# Lora_LR1262_Node__Board_V1_0_1.net
KiCad netlist of a schematic drawn in EAGLE
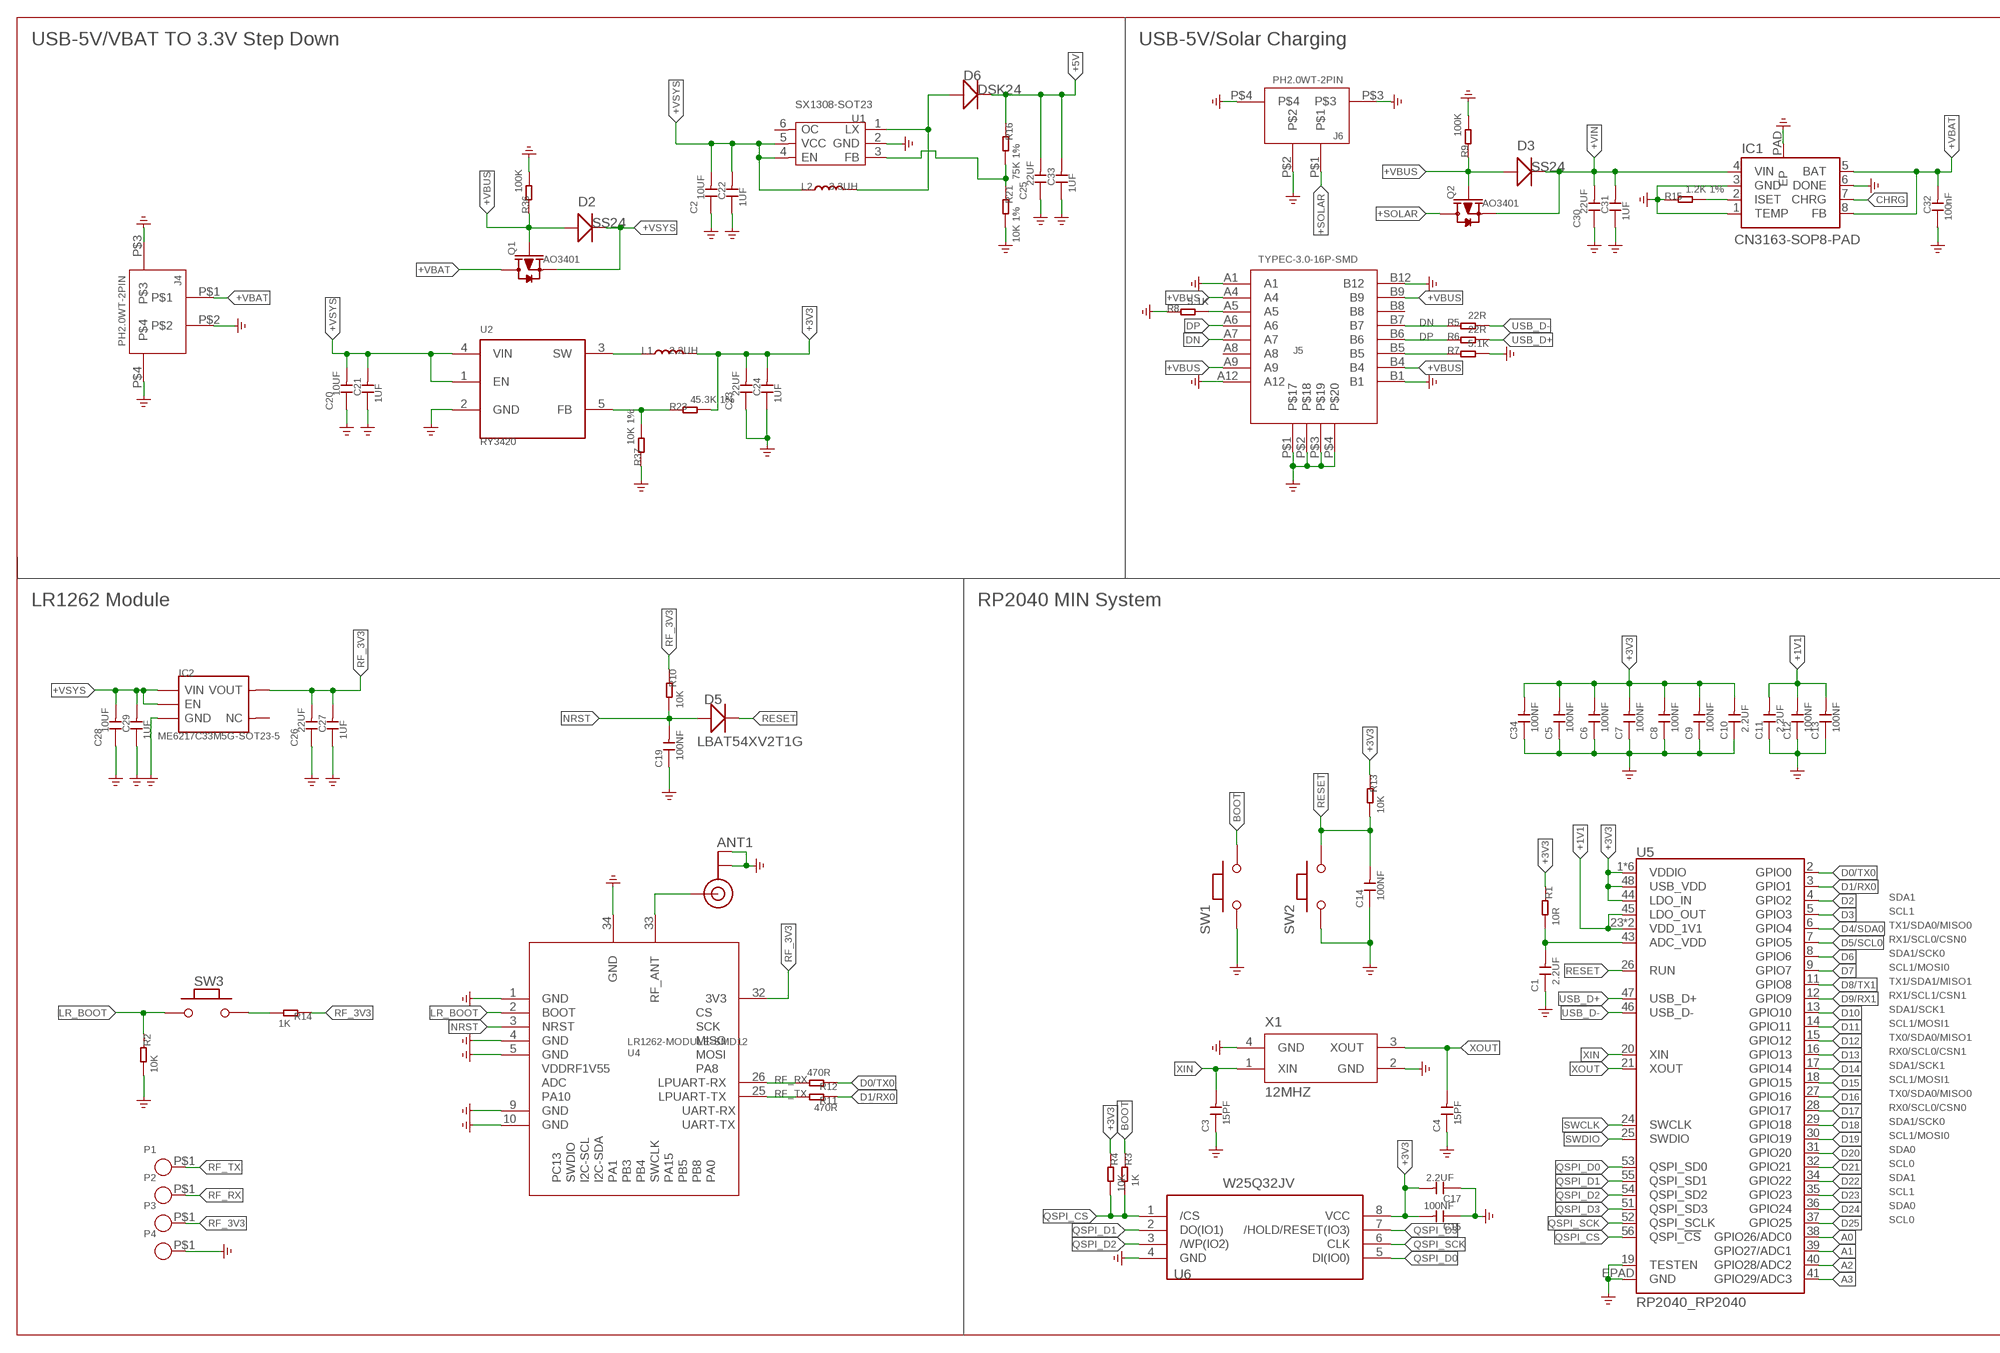
[diagram p0: schematic, sheet 1, part 1 of 2]
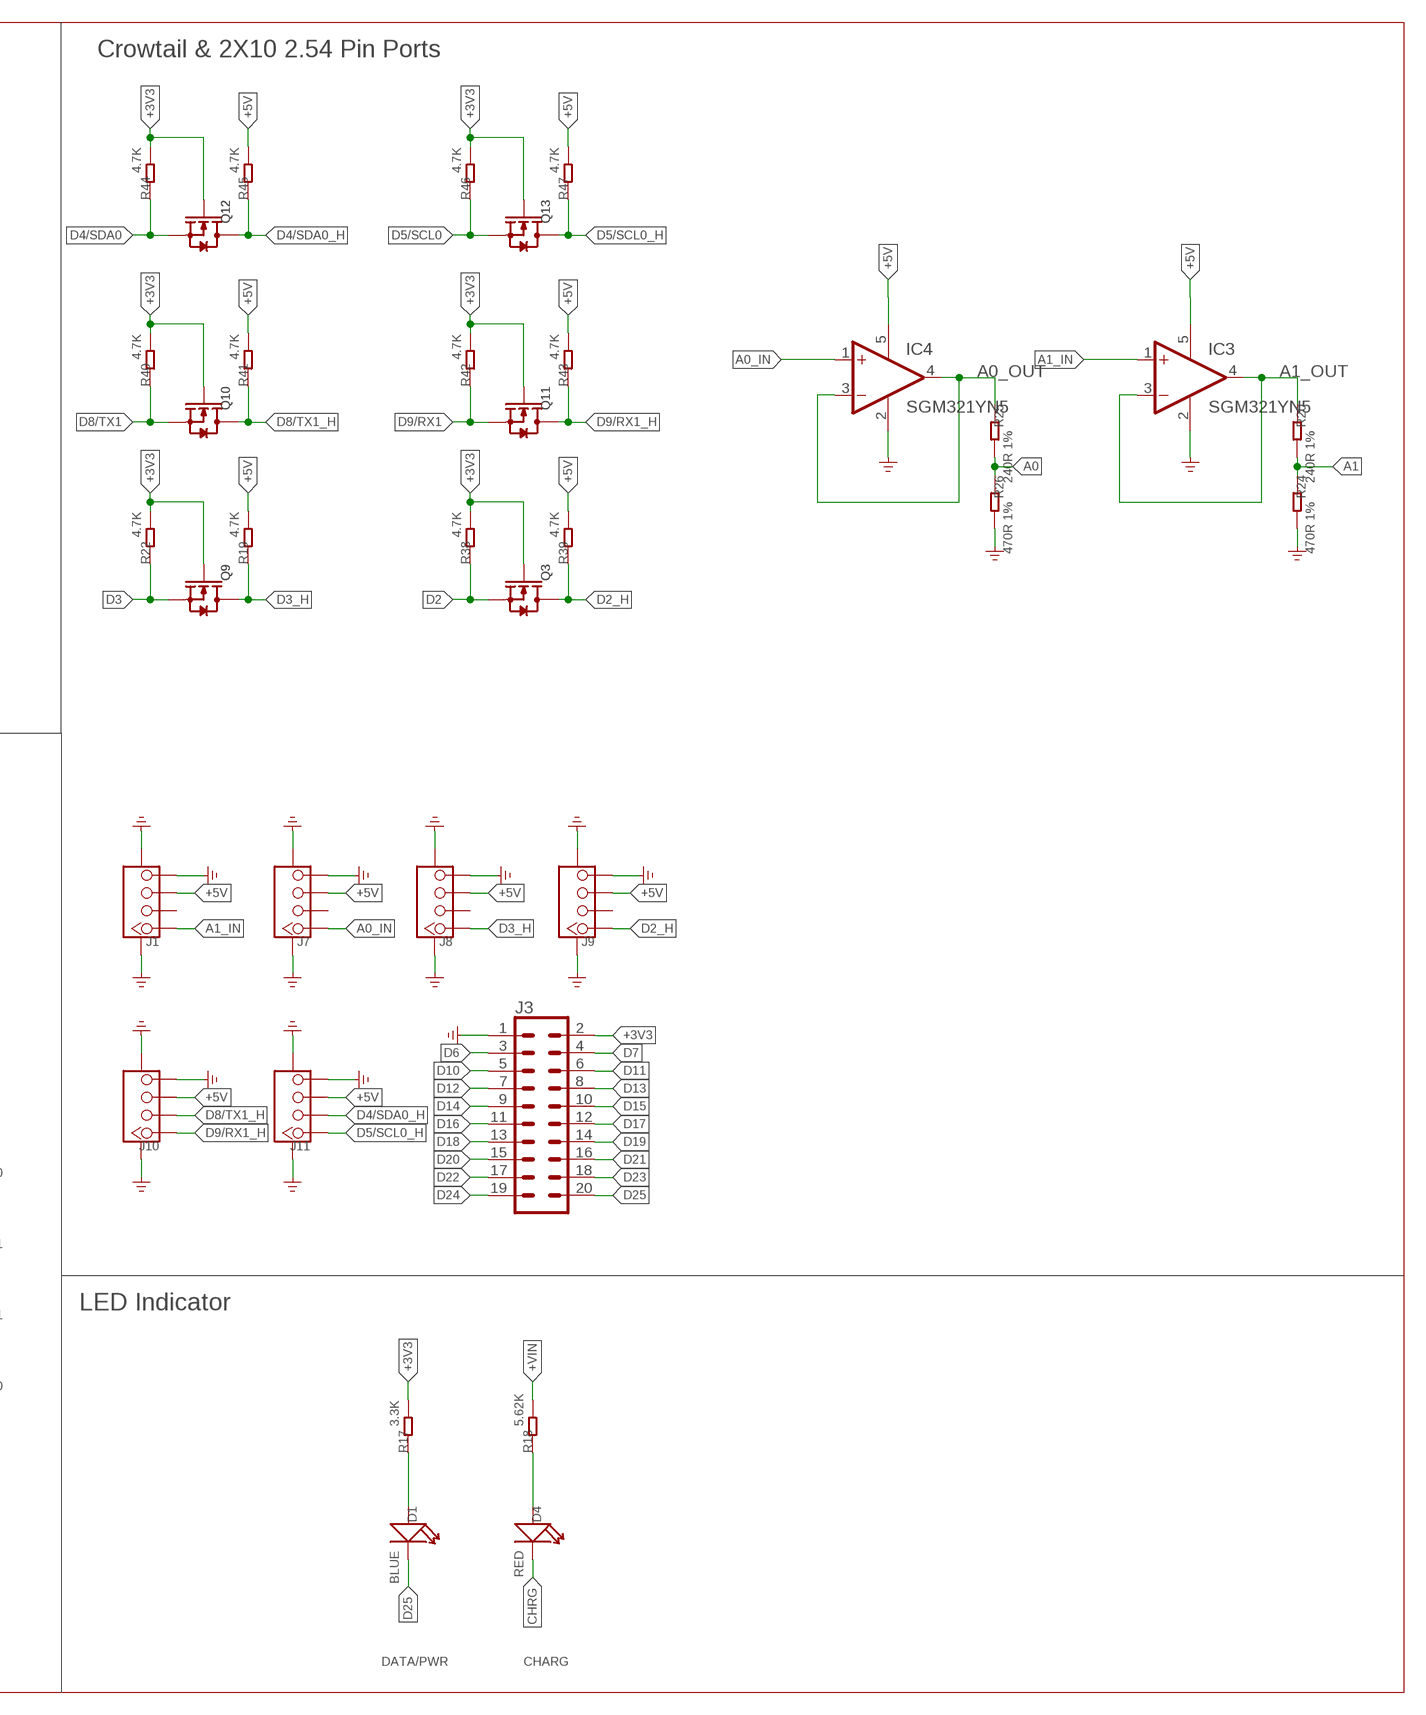
[diagram p1: schematic, sheet 1, part 2 of 2]

(export (version "E")
  (design (tool "Eeschema 10.0.6"))
  (components
    (comp (ref "ANT1")
      (value "SPARKFUN2_U.FL")
      (footprint "eagle-import:SPARKFUN2_U.FL")
      (libsource (lib "eagle-import") (part "SPARKFUN2_U.FL"))
    )
    (comp (ref "C1")
      (value "2.2UF")
      (footprint "eagle-import:0402")
      (libsource (lib "eagle-import") (part "CAPC0402-1"))
    )
    (comp (ref "C2")
      (value "10UF")
      (footprint "eagle-import:C0805")
      (libsource (lib "eagle-import") (part "C0805"))
    )
    (comp (ref "C3")
      (value "15PF")
      (footprint "eagle-import:0402")
      (libsource (lib "eagle-import") (part "CAPC0402-1"))
    )
    (comp (ref "C4")
      (value "15PF")
      (footprint "eagle-import:0402")
      (libsource (lib "eagle-import") (part "CAPC0402-1"))
    )
    (comp (ref "C5")
      (value "100NF")
      (footprint "eagle-import:0402")
      (libsource (lib "eagle-import") (part "CAPC0402-1"))
    )
    (comp (ref "C6")
      (value "100NF")
      (footprint "eagle-import:0402")
      (libsource (lib "eagle-import") (part "CAPC0402-1"))
    )
    (comp (ref "C7")
      (value "100NF")
      (footprint "eagle-import:0402")
      (libsource (lib "eagle-import") (part "CAPC0402-1"))
    )
    (comp (ref "C8")
      (value "100NF")
      (footprint "eagle-import:0402")
      (libsource (lib "eagle-import") (part "CAPC0402-1"))
    )
    (comp (ref "C9")
      (value "100NF")
      (footprint "eagle-import:0402")
      (libsource (lib "eagle-import") (part "CAPC0402-1"))
    )
    (comp (ref "C10")
      (value "2.2UF")
      (footprint "eagle-import:0402")
      (libsource (lib "eagle-import") (part "CAPC0402-1"))
    )
    (comp (ref "C11")
      (value "2.2UF")
      (footprint "eagle-import:0402")
      (libsource (lib "eagle-import") (part "CAPC0402-1"))
    )
    (comp (ref "C12")
      (value "100NF")
      (footprint "eagle-import:0402")
      (libsource (lib "eagle-import") (part "CAPC0402-1"))
    )
    (comp (ref "C13")
      (value "100NF")
      (footprint "eagle-import:0402")
      (libsource (lib "eagle-import") (part "CAPC0402-1"))
    )
    (comp (ref "C14")
      (value "100NF")
      (footprint "eagle-import:0402")
      (libsource (lib "eagle-import") (part "CAPC0402-1"))
    )
    (comp (ref "C15")
      (value "100NF")
      (footprint "eagle-import:0402")
      (libsource (lib "eagle-import") (part "CAPC0402-1"))
    )
    (comp (ref "C17")
      (value "2.2UF")
      (footprint "eagle-import:0402")
      (libsource (lib "eagle-import") (part "CAPC0402-1"))
    )
    (comp (ref "C19")
      (value "100NF")
      (footprint "eagle-import:0402")
      (libsource (lib "eagle-import") (part "CAPC0402-1"))
    )
    (comp (ref "C20")
      (value "10UF")
      (footprint "eagle-import:C0805")
      (libsource (lib "eagle-import") (part "C0805"))
    )
    (comp (ref "C21")
      (value "1UF")
      (footprint "eagle-import:C0603")
      (libsource (lib "eagle-import") (part "C0603"))
    )
    (comp (ref "C22")
      (value "1UF")
      (footprint "eagle-import:C0603")
      (libsource (lib "eagle-import") (part "C0603"))
    )
    (comp (ref "C23")
      (value "22UF")
      (footprint "eagle-import:C0805")
      (libsource (lib "eagle-import") (part "C0805"))
    )
    (comp (ref "C24")
      (value "1UF")
      (footprint "eagle-import:C0603")
      (libsource (lib "eagle-import") (part "C0603"))
    )
    (comp (ref "C25")
      (value "22UF")
      (footprint "eagle-import:C0805")
      (libsource (lib "eagle-import") (part "C0805"))
    )
    (comp (ref "C26")
      (value "22UF")
      (footprint "eagle-import:C0805")
      (libsource (lib "eagle-import") (part "C0805"))
    )
    (comp (ref "C27")
      (value "1UF")
      (footprint "eagle-import:C0603")
      (libsource (lib "eagle-import") (part "C0603"))
    )
    (comp (ref "C28")
      (value "10UF")
      (footprint "eagle-import:C0805")
      (libsource (lib "eagle-import") (part "C0805"))
    )
    (comp (ref "C29")
      (value "1UF")
      (footprint "eagle-import:C0603")
      (libsource (lib "eagle-import") (part "C0603"))
    )
    (comp (ref "C30")
      (value "22UF")
      (footprint "eagle-import:C0805")
      (libsource (lib "eagle-import") (part "C0805"))
    )
    (comp (ref "C31")
      (value "1UF")
      (footprint "eagle-import:C0603")
      (libsource (lib "eagle-import") (part "C0603"))
    )
    (comp (ref "C32")
      (value "100nF")
      (footprint "eagle-import:C0603")
      (libsource (lib "eagle-import") (part "C0603"))
    )
    (comp (ref "C33")
      (value "1UF")
      (footprint "eagle-import:C0603")
      (libsource (lib "eagle-import") (part "C0603"))
    )
    (comp (ref "C34")
      (value "100NF")
      (footprint "eagle-import:0402")
      (libsource (lib "eagle-import") (part "CAPC0402-1"))
    )
    (comp (ref "D1")
      (value "BLUE")
      (footprint "eagle-import:LED0603")
      (libsource (lib "eagle-import") (part "LED-SMT0603"))
    )
    (comp (ref "D2")
      (value "SS24")
      (footprint "eagle-import:SMA")
      (libsource (lib "eagle-import") (part "DIODEB130L-13-F"))
    )
    (comp (ref "D3")
      (value "SS24")
      (footprint "eagle-import:SMA")
      (libsource (lib "eagle-import") (part "DIODEB130L-13-F"))
    )
    (comp (ref "D4")
      (value "RED")
      (footprint "eagle-import:LED0603")
      (libsource (lib "eagle-import") (part "LED-SMT0603"))
    )
    (comp (ref "D5")
      (value "LBAT54XV2T1G")
      (footprint "eagle-import:D_SOD523")
      (libsource (lib "eagle-import") (part "DIODE0603"))
    )
    (comp (ref "D6")
      (value "DSK24")
      (footprint "eagle-import:D_SOD123FL")
      (libsource (lib "eagle-import") (part "DIODE"))
    )
    (comp (ref "IC1")
      (value "CN3163-SOP8-PAD")
      (footprint "eagle-import:SOP8-PAD")
      (libsource (lib "eagle-import") (part "CN3163-SOP8-PAD"))
    )
    (comp (ref "IC2")
      (value "ME6217C33M5G-SOT23-5")
      (footprint "eagle-import:IC_SOT23-5")
      (libsource (lib "eagle-import") (part "ME6217C33M5G-SOT23-5"))
    )
    (comp (ref "IC3")
      (value "SGM321YN5")
      (footprint "eagle-import:SOT23-5")
      (libsource (lib "eagle-import") (part "LM321?MF"))
    )
    (comp (ref "IC4")
      (value "SGM321YN5")
      (footprint "eagle-import:SOT23-5")
      (libsource (lib "eagle-import") (part "LM321?MF"))
    )
    (comp (ref "J1")
      (value "CONNECTOR_TWIG-4P-2.0-SMD-FEMALE-REINFORCE90D")
      (footprint "eagle-import:CONNECTOR_4P-SMD-2.0-90D")
      (libsource (lib "eagle-import") (part "CONNECTOR_TWIG-4P-2.0-SMD-FEMALE-REINFORCE90D"))
    )
    (comp (ref "J3")
      (value "CONN_10X22X10-DSY-P2.54")
      (footprint "eagle-import:2X10-DSY-P2.54")
      (libsource (lib "eagle-import") (part "CONN_10X22X10-DSY-P2.54"))
    )
    (comp (ref "J4")
      (value "PH2.0WT-2PIN")
      (footprint "eagle-import:PH2.0WT-2PIN")
      (libsource (lib "eagle-import") (part "PH2.0WT-2PIN"))
    )
    (comp (ref "J5")
      (value "TYPEC-3.0-16P-SMD")
      (footprint "eagle-import:KEVIN_3.0TYPEC-SMD")
      (libsource (lib "eagle-import") (part "TYPEC-3.0-16P-SMD"))
    )
    (comp (ref "J6")
      (value "PH2.0WT-2PIN")
      (footprint "eagle-import:PH2.0WT-2PIN")
      (libsource (lib "eagle-import") (part "PH2.0WT-2PIN"))
    )
    (comp (ref "J7")
      (value "CONNECTOR_TWIG-4P-2.0-SMD-FEMALE-REINFORCE90D")
      (footprint "eagle-import:CONNECTOR_4P-SMD-2.0-90D")
      (libsource (lib "eagle-import") (part "CONNECTOR_TWIG-4P-2.0-SMD-FEMALE-REINFORCE90D"))
    )
    (comp (ref "J8")
      (value "CONNECTOR_TWIG-4P-2.0-SMD-FEMALE-REINFORCE90D")
      (footprint "eagle-import:CONNECTOR_4P-SMD-2.0-90D")
      (libsource (lib "eagle-import") (part "CONNECTOR_TWIG-4P-2.0-SMD-FEMALE-REINFORCE90D"))
    )
    (comp (ref "J9")
      (value "CONNECTOR_TWIG-4P-2.0-SMD-FEMALE-REINFORCE90D")
      (footprint "eagle-import:CONNECTOR_4P-SMD-2.0-90D")
      (libsource (lib "eagle-import") (part "CONNECTOR_TWIG-4P-2.0-SMD-FEMALE-REINFORCE90D"))
    )
    (comp (ref "J10")
      (value "CONNECTOR_TWIG-4P-2.0-SMD-FEMALE-REINFORCE90D")
      (footprint "eagle-import:CONNECTOR_4P-SMD-2.0-90D")
      (libsource (lib "eagle-import") (part "CONNECTOR_TWIG-4P-2.0-SMD-FEMALE-REINFORCE90D"))
    )
    (comp (ref "J11")
      (value "CONNECTOR_TWIG-4P-2.0-SMD-FEMALE-REINFORCE90D")
      (footprint "eagle-import:CONNECTOR_4P-SMD-2.0-90D")
      (libsource (lib "eagle-import") (part "CONNECTOR_TWIG-4P-2.0-SMD-FEMALE-REINFORCE90D"))
    )
    (comp (ref "L1")
      (value "2.2UH")
      (footprint "eagle-import:L0420")
      (libsource (lib "eagle-import") (part "LL0420"))
    )
    (comp (ref "L2")
      (value "3.3UH")
      (footprint "eagle-import:L0420")
      (libsource (lib "eagle-import") (part "LL0420"))
    )
    (comp (ref "P1")
      (value "TEST_PADPAD-1.5MM")
      (footprint "eagle-import:TEST_PAD-1.5MM")
      (libsource (lib "eagle-import") (part "TEST_PADPAD-1.5MM"))
    )
    (comp (ref "P2")
      (value "TEST_PADPAD-1.5MM")
      (footprint "eagle-import:TEST_PAD-1.5MM")
      (libsource (lib "eagle-import") (part "TEST_PADPAD-1.5MM"))
    )
    (comp (ref "P3")
      (value "TEST_PADPAD-1.5MM")
      (footprint "eagle-import:TEST_PAD-1.5MM")
      (libsource (lib "eagle-import") (part "TEST_PADPAD-1.5MM"))
    )
    (comp (ref "P4")
      (value "TEST_PADPAD-1.5MM")
      (footprint "eagle-import:TEST_PAD-1.5MM")
      (libsource (lib "eagle-import") (part "TEST_PADPAD-1.5MM"))
    )
    (comp (ref "Q1")
      (value "AO3401")
      (footprint "eagle-import:PMOS_SOT23")
      (libsource (lib "eagle-import") (part "MOSFET-PSOT23"))
    )
    (comp (ref "Q2")
      (value "AO3401")
      (footprint "eagle-import:PMOS_SOT23")
      (libsource (lib "eagle-import") (part "MOSFET-PSOT23"))
    )
    (comp (ref "Q3")
      (value "MOSFET-NSI1304BDL")
      (footprint "eagle-import:MOS_SOT323")
      (libsource (lib "eagle-import") (part "MOSFET-NSI1304BDL"))
    )
    (comp (ref "Q9")
      (value "MOSFET-NSI1304BDL")
      (footprint "eagle-import:MOS_SOT323")
      (libsource (lib "eagle-import") (part "MOSFET-NSI1304BDL"))
    )
    (comp (ref "Q10")
      (value "MOSFET-NSI1304BDL")
      (footprint "eagle-import:MOS_SOT323")
      (libsource (lib "eagle-import") (part "MOSFET-NSI1304BDL"))
    )
    (comp (ref "Q11")
      (value "MOSFET-NSI1304BDL")
      (footprint "eagle-import:MOS_SOT323")
      (libsource (lib "eagle-import") (part "MOSFET-NSI1304BDL"))
    )
    (comp (ref "Q12")
      (value "MOSFET-NSI1304BDL")
      (footprint "eagle-import:MOS_SOT323")
      (libsource (lib "eagle-import") (part "MOSFET-NSI1304BDL"))
    )
    (comp (ref "Q13")
      (value "MOSFET-NSI1304BDL")
      (footprint "eagle-import:MOS_SOT323")
      (libsource (lib "eagle-import") (part "MOSFET-NSI1304BDL"))
    )
    (comp (ref "R1")
      (value "10R")
      (footprint "eagle-import:R0402")
      (libsource (lib "eagle-import") (part "RES-0402"))
    )
    (comp (ref "R2")
      (value "10K")
      (footprint "eagle-import:R0402")
      (libsource (lib "eagle-import") (part "RES-0402"))
    )
    (comp (ref "R3")
      (value "1K")
      (footprint "eagle-import:R0402")
      (libsource (lib "eagle-import") (part "RES-0402"))
    )
    (comp (ref "R4")
      (value "10K")
      (footprint "eagle-import:R0402")
      (libsource (lib "eagle-import") (part "RES-0402"))
    )
    (comp (ref "R5")
      (value "22R")
      (footprint "eagle-import:R0402")
      (libsource (lib "eagle-import") (part "RES-0402"))
    )
    (comp (ref "R6")
      (value "22R")
      (footprint "eagle-import:R0402")
      (libsource (lib "eagle-import") (part "RES-0402"))
    )
    (comp (ref "R7")
      (value "5.1K")
      (footprint "eagle-import:R0402")
      (libsource (lib "eagle-import") (part "RES-0402"))
    )
    (comp (ref "R8")
      (value "5.1K")
      (footprint "eagle-import:R0402")
      (libsource (lib "eagle-import") (part "RES-0402"))
    )
    (comp (ref "R9")
      (value "100K")
      (footprint "eagle-import:R0402")
      (libsource (lib "eagle-import") (part "RES-0402"))
    )
    (comp (ref "R10")
      (value "10K")
      (footprint "eagle-import:R0402")
      (libsource (lib "eagle-import") (part "RES-0402"))
    )
    (comp (ref "R11")
      (value "470R")
      (footprint "eagle-import:R0402")
      (libsource (lib "eagle-import") (part "RES-0402"))
    )
    (comp (ref "R12")
      (value "470R")
      (footprint "eagle-import:R0402")
      (libsource (lib "eagle-import") (part "RES-0402"))
    )
    (comp (ref "R13")
      (value "10K")
      (footprint "eagle-import:R0402")
      (libsource (lib "eagle-import") (part "RES-0402"))
    )
    (comp (ref "R14")
      (value "1K")
      (footprint "eagle-import:R0402")
      (libsource (lib "eagle-import") (part "RES-0402"))
    )
    (comp (ref "R15")
      (value "1.2K 1%")
      (footprint "eagle-import:R0402")
      (libsource (lib "eagle-import") (part "RES-0402"))
    )
    (comp (ref "R16")
      (value "75K 1%")
      (footprint "eagle-import:R0402")
      (libsource (lib "eagle-import") (part "RES-0402"))
    )
    (comp (ref "R17")
      (value "3.3K")
      (footprint "eagle-import:R0402")
      (libsource (lib "eagle-import") (part "RES-0402"))
    )
    (comp (ref "R18")
      (value "5.62K")
      (footprint "eagle-import:R0402")
      (libsource (lib "eagle-import") (part "RES-0402"))
    )
    (comp (ref "R19")
      (value "4.7K")
      (footprint "eagle-import:R0402")
      (libsource (lib "eagle-import") (part "RES-0402"))
    )
    (comp (ref "R20")
      (value "240R 1%")
      (footprint "eagle-import:R0402")
      (libsource (lib "eagle-import") (part "RES-0402"))
    )
    (comp (ref "R21")
      (value "10K 1%")
      (footprint "eagle-import:R0402")
      (libsource (lib "eagle-import") (part "RES-0402"))
    )
    (comp (ref "R22")
      (value "4.7K")
      (footprint "eagle-import:R0402")
      (libsource (lib "eagle-import") (part "RES-0402"))
    )
    (comp (ref "R23")
      (value "45.3K 1%")
      (footprint "eagle-import:R0402")
      (libsource (lib "eagle-import") (part "RES-0402"))
    )
    (comp (ref "R24")
      (value "470R 1%")
      (footprint "eagle-import:R0402")
      (libsource (lib "eagle-import") (part "RES-0402"))
    )
    (comp (ref "R25")
      (value "240R 1%")
      (footprint "eagle-import:R0402")
      (libsource (lib "eagle-import") (part "RES-0402"))
    )
    (comp (ref "R26")
      (value "470R 1%")
      (footprint "eagle-import:R0402")
      (libsource (lib "eagle-import") (part "RES-0402"))
    )
    (comp (ref "R36")
      (value "100K")
      (footprint "eagle-import:R0402")
      (libsource (lib "eagle-import") (part "RES-0402"))
    )
    (comp (ref "R37")
      (value "10K 1%")
      (footprint "eagle-import:R0402")
      (libsource (lib "eagle-import") (part "RES-0402"))
    )
    (comp (ref "R38")
      (value "4.7K")
      (footprint "eagle-import:R0402")
      (libsource (lib "eagle-import") (part "RES-0402"))
    )
    (comp (ref "R39")
      (value "4.7K")
      (footprint "eagle-import:R0402")
      (libsource (lib "eagle-import") (part "RES-0402"))
    )
    (comp (ref "R40")
      (value "4.7K")
      (footprint "eagle-import:R0402")
      (libsource (lib "eagle-import") (part "RES-0402"))
    )
    (comp (ref "R41")
      (value "4.7K")
      (footprint "eagle-import:R0402")
      (libsource (lib "eagle-import") (part "RES-0402"))
    )
    (comp (ref "R42")
      (value "4.7K")
      (footprint "eagle-import:R0402")
      (libsource (lib "eagle-import") (part "RES-0402"))
    )
    (comp (ref "R43")
      (value "4.7K")
      (footprint "eagle-import:R0402")
      (libsource (lib "eagle-import") (part "RES-0402"))
    )
    (comp (ref "R44")
      (value "4.7K")
      (footprint "eagle-import:R0402")
      (libsource (lib "eagle-import") (part "RES-0402"))
    )
    (comp (ref "R45")
      (value "4.7K")
      (footprint "eagle-import:R0402")
      (libsource (lib "eagle-import") (part "RES-0402"))
    )
    (comp (ref "R46")
      (value "4.7K")
      (footprint "eagle-import:R0402")
      (libsource (lib "eagle-import") (part "RES-0402"))
    )
    (comp (ref "R47")
      (value "4.7K")
      (footprint "eagle-import:R0402")
      (libsource (lib "eagle-import") (part "RES-0402"))
    )
    (comp (ref "SW1")
      (value "MYSMD_PB157_4.3X3")
      (footprint "eagle-import:MYSMD_157SW")
      (libsource (lib "eagle-import") (part "MYSMD_PB157_4.3X3"))
    )
    (comp (ref "SW2")
      (value "MYSMD_PB157_4.3X3")
      (footprint "eagle-import:MYSMD_157SW")
      (libsource (lib "eagle-import") (part "MYSMD_PB157_4.3X3"))
    )
    (comp (ref "SW3")
      (value "MYSMD_PB157_4.3X3")
      (footprint "eagle-import:MYSMD_157SW")
      (libsource (lib "eagle-import") (part "MYSMD_PB157_4.3X3"))
    )
    (comp (ref "U1")
      (value "SX1308-SOT23")
      (footprint "eagle-import:STUDY_SOT23-6L")
      (libsource (lib "eagle-import") (part "STUDY_SX1301"))
    )
    (comp (ref "U2")
      (value "RY3420")
      (footprint "eagle-import:IC_SOT23-5")
      (libsource (lib "eagle-import") (part "HM3416H"))
    )
    (comp (ref "U4")
      (value "LR1262-MODULE-SMD12")
      (footprint "eagle-import:LR1262-MODULE-SMD12")
      (libsource (lib "eagle-import") (part "LR1262-MODULE-SMD12"))
    )
    (comp (ref "U5")
      (value "RP2040_RP2040")
      (footprint "eagle-import:RP2040_QFN-56")
      (libsource (lib "eagle-import") (part "RP2040_RP2040"))
    )
    (comp (ref "U6")
      (value "W25Q32JV")
      (footprint "eagle-import:SELF_SOIC-8-208MIL")
      (libsource (lib "eagle-import") (part "W25Q32JV"))
    )
    (comp (ref "X1")
      (value "12MHZ")
      (footprint "eagle-import:SMD3225")
      (libsource (lib "eagle-import") (part "XTAL-SMD3225"))
    )
  )
  (nets
    (net (code "1") (name "+1V1") (class "Default")
      (node (ref "C11") (pin "2") (pinfunction "2_2") (pintype "passive"))
      (node (ref "C12") (pin "2") (pinfunction "2_2") (pintype "passive"))
      (node (ref "C13") (pin "2") (pinfunction "2_2") (pintype "passive"))
      (node (ref "U5") (pin "23") (pinfunction "VDD_1V1_23") (pintype "bidirectional"))
      (node (ref "U5") (pin "45") (pinfunction "LDO_OUT_45") (pintype "bidirectional"))
      (node (ref "U5") (pin "50") (pinfunction "VDD_1V1_50") (pintype "bidirectional"))
    )
    (net (code "2") (name "+3V3") (class "Default")
      (node (ref "C10") (pin "2") (pinfunction "2_2") (pintype "passive"))
      (node (ref "C15") (pin "2") (pinfunction "2_2") (pintype "passive"))
      (node (ref "C17") (pin "2") (pinfunction "2_2") (pintype "passive"))
      (node (ref "C23") (pin "2") (pinfunction "2_2") (pintype "passive"))
      (node (ref "C24") (pin "2") (pinfunction "2_2") (pintype "passive"))
      (node (ref "C34") (pin "2") (pinfunction "2_2") (pintype "passive"))
      (node (ref "C5") (pin "2") (pinfunction "2_2") (pintype "passive"))
      (node (ref "C6") (pin "2") (pinfunction "2_2") (pintype "passive"))
      (node (ref "C7") (pin "2") (pinfunction "2_2") (pintype "passive"))
      (node (ref "C8") (pin "2") (pinfunction "2_2") (pintype "passive"))
      (node (ref "C9") (pin "2") (pinfunction "2_2") (pintype "passive"))
      (node (ref "J3") (pin "2") (pinfunction "2_2") (pintype "passive"))
      (node (ref "L1") (pin "2") (pinfunction "2_2") (pintype "passive"))
      (node (ref "Q10") (pin "1") (pinfunction "G_1") (pintype "passive"))
      (node (ref "Q11") (pin "1") (pinfunction "G_1") (pintype "passive"))
      (node (ref "Q12") (pin "1") (pinfunction "G_1") (pintype "passive"))
      (node (ref "Q13") (pin "1") (pinfunction "G_1") (pintype "passive"))
      (node (ref "Q3") (pin "1") (pinfunction "G_1") (pintype "passive"))
      (node (ref "Q9") (pin "1") (pinfunction "G_1") (pintype "passive"))
      (node (ref "R1") (pin "1") (pinfunction "1_1") (pintype "passive"))
      (node (ref "R13") (pin "1") (pinfunction "1_1") (pintype "passive"))
      (node (ref "R17") (pin "2") (pinfunction "2_2") (pintype "passive"))
      (node (ref "R22") (pin "2") (pinfunction "2_2") (pintype "passive"))
      (node (ref "R23") (pin "2") (pinfunction "2_2") (pintype "passive"))
      (node (ref "R38") (pin "2") (pinfunction "2_2") (pintype "passive"))
      (node (ref "R4") (pin "1") (pinfunction "1_1") (pintype "passive"))
      (node (ref "R40") (pin "2") (pinfunction "2_2") (pintype "passive"))
      (node (ref "R42") (pin "2") (pinfunction "2_2") (pintype "passive"))
      (node (ref "R44") (pin "2") (pinfunction "2_2") (pintype "passive"))
      (node (ref "R46") (pin "2") (pinfunction "2_2") (pintype "passive"))
      (node (ref "U5") (pin "1") (pinfunction "VDDIO_1") (pintype "bidirectional"))
      (node (ref "U5") (pin "10") (pinfunction "VDDIO_10") (pintype "bidirectional"))
      (node (ref "U5") (pin "22") (pinfunction "VDDIO_22") (pintype "bidirectional"))
      (node (ref "U5") (pin "33") (pinfunction "VDDIO_33") (pintype "bidirectional"))
      (node (ref "U5") (pin "42") (pinfunction "VDDIO_42") (pintype "bidirectional"))
      (node (ref "U5") (pin "44") (pinfunction "LDO_IN_44") (pintype "bidirectional"))
      (node (ref "U5") (pin "48") (pinfunction "USB_VDD_48") (pintype "bidirectional"))
      (node (ref "U5") (pin "49") (pinfunction "VDDIO_49") (pintype "bidirectional"))
      (node (ref "U6") (pin "8") (pinfunction "VCC_8") (pintype "bidirectional"))
    )
    (net (code "3") (name "+5V") (class "Default")
      (node (ref "C25") (pin "2") (pinfunction "2_2") (pintype "passive"))
      (node (ref "C33") (pin "2") (pinfunction "2_2") (pintype "passive"))
      (node (ref "D6") (pin "-") (pinfunction "-_-") (pintype "passive"))
      (node (ref "IC3") (pin "5") (pinfunction "V+_5") (pintype "power_in"))
      (node (ref "IC4") (pin "5") (pinfunction "V+_5") (pintype "power_in"))
      (node (ref "J1") (pin "3") (pinfunction "3_3") (pintype "bidirectional"))
      (node (ref "J10") (pin "3") (pinfunction "3_3") (pintype "bidirectional"))
      (node (ref "J11") (pin "3") (pinfunction "3_3") (pintype "bidirectional"))
      (node (ref "J7") (pin "3") (pinfunction "3_3") (pintype "bidirectional"))
      (node (ref "J8") (pin "3") (pinfunction "3_3") (pintype "bidirectional"))
      (node (ref "J9") (pin "3") (pinfunction "3_3") (pintype "bidirectional"))
      (node (ref "R16") (pin "1") (pinfunction "1_1") (pintype "passive"))
      (node (ref "R19") (pin "2") (pinfunction "2_2") (pintype "passive"))
      (node (ref "R39") (pin "2") (pinfunction "2_2") (pintype "passive"))
      (node (ref "R41") (pin "2") (pinfunction "2_2") (pintype "passive"))
      (node (ref "R43") (pin "2") (pinfunction "2_2") (pintype "passive"))
      (node (ref "R45") (pin "2") (pinfunction "2_2") (pintype "passive"))
      (node (ref "R47") (pin "2") (pinfunction "2_2") (pintype "passive"))
    )
    (net (code "4") (name "+SOLAR") (class "Default")
      (node (ref "J6") (pin "P$1") (pinfunction "P$1_P$1") (pintype "bidirectional"))
      (node (ref "Q2") (pin "3") (pinfunction "D_3") (pintype "passive"))
    )
    (net (code "5") (name "+VBAT") (class "Default")
      (node (ref "C32") (pin "2") (pinfunction "2_2") (pintype "passive"))
      (node (ref "IC1") (pin "5") (pinfunction "BAT_5") (pintype "bidirectional"))
      (node (ref "IC1") (pin "8") (pinfunction "FB_8") (pintype "bidirectional"))
      (node (ref "J4") (pin "P$1") (pinfunction "P$1_P$1") (pintype "bidirectional"))
      (node (ref "Q1") (pin "3") (pinfunction "D_3") (pintype "passive"))
    )
    (net (code "6") (name "+VBUS") (class "Default")
      (node (ref "D2") (pin "2") (pinfunction "+_2") (pintype "passive"))
      (node (ref "D3") (pin "2") (pinfunction "+_2") (pintype "passive"))
      (node (ref "J5") (pin "A4") (pinfunction "A4_A4") (pintype "bidirectional"))
      (node (ref "J5") (pin "A9") (pinfunction "A9_A9") (pintype "bidirectional"))
      (node (ref "J5") (pin "B4") (pinfunction "B4_B4") (pintype "bidirectional"))
      (node (ref "J5") (pin "B9") (pinfunction "B9_B9") (pintype "bidirectional"))
      (node (ref "Q1") (pin "1") (pinfunction "G_1") (pintype "passive"))
      (node (ref "Q2") (pin "1") (pinfunction "G_1") (pintype "passive"))
      (node (ref "R36") (pin "1") (pinfunction "1_1") (pintype "passive"))
      (node (ref "R9") (pin "1") (pinfunction "1_1") (pintype "passive"))
    )
    (net (code "7") (name "+VIN") (class "Default")
      (node (ref "C30") (pin "2") (pinfunction "2_2") (pintype "passive"))
      (node (ref "C31") (pin "2") (pinfunction "2_2") (pintype "passive"))
      (node (ref "D3") (pin "1") (pinfunction "-_1") (pintype "passive"))
      (node (ref "IC1") (pin "4") (pinfunction "VIN_4") (pintype "bidirectional"))
      (node (ref "Q2") (pin "2") (pinfunction "S_2") (pintype "passive"))
      (node (ref "R18") (pin "2") (pinfunction "2_2") (pintype "passive"))
    )
    (net (code "8") (name "+VSYS") (class "Default")
      (node (ref "C2") (pin "2") (pinfunction "2_2") (pintype "passive"))
      (node (ref "C20") (pin "2") (pinfunction "2_2") (pintype "passive"))
      (node (ref "C21") (pin "2") (pinfunction "2_2") (pintype "passive"))
      (node (ref "C22") (pin "2") (pinfunction "2_2") (pintype "passive"))
      (node (ref "C28") (pin "2") (pinfunction "2_2") (pintype "passive"))
      (node (ref "C29") (pin "2") (pinfunction "2_2") (pintype "passive"))
      (node (ref "D2") (pin "1") (pinfunction "-_1") (pintype "passive"))
      (node (ref "IC2") (pin "1") (pinfunction "VIN_1") (pintype "bidirectional"))
      (node (ref "IC2") (pin "3") (pinfunction "EN_3") (pintype "bidirectional"))
      (node (ref "L2") (pin "1") (pinfunction "1_1") (pintype "passive"))
      (node (ref "Q1") (pin "2") (pinfunction "S_2") (pintype "passive"))
      (node (ref "U1") (pin "4") (pinfunction "EN_4") (pintype "bidirectional"))
      (node (ref "U1") (pin "5") (pinfunction "VCC_5") (pintype "bidirectional"))
      (node (ref "U2") (pin "1") (pinfunction "EN_1") (pintype "bidirectional"))
      (node (ref "U2") (pin "4") (pinfunction "VIN_4") (pintype "bidirectional"))
    )
    (net (code "9") (name "/A0_OUT") (class "Default")
      (node (ref "IC4") (pin "3") (pinfunction "-IN_3") (pintype "input"))
      (node (ref "IC4") (pin "4") (pinfunction "OUT_4") (pintype "output"))
      (node (ref "R25") (pin "1") (pinfunction "1_1") (pintype "passive"))
    )
    (net (code "10") (name "/A1_OUT") (class "Default")
      (node (ref "IC3") (pin "3") (pinfunction "-IN_3") (pintype "input"))
      (node (ref "IC3") (pin "4") (pinfunction "OUT_4") (pintype "output"))
      (node (ref "R20") (pin "1") (pinfunction "1_1") (pintype "passive"))
    )
    (net (code "11") (name "A0") (class "Default")
      (node (ref "R25") (pin "2") (pinfunction "2_2") (pintype "passive"))
      (node (ref "R26") (pin "1") (pinfunction "1_1") (pintype "passive"))
      (node (ref "U5") (pin "38") (pinfunction "GPIO26/ADC0_38") (pintype "bidirectional"))
    )
    (net (code "12") (name "A0_IN") (class "Default")
      (node (ref "IC4") (pin "1") (pinfunction "+IN_1") (pintype "input"))
      (node (ref "J7") (pin "1") (pinfunction "1_1") (pintype "bidirectional"))
    )
    (net (code "13") (name "A1") (class "Default")
      (node (ref "R20") (pin "2") (pinfunction "2_2") (pintype "passive"))
      (node (ref "R24") (pin "1") (pinfunction "1_1") (pintype "passive"))
      (node (ref "U5") (pin "39") (pinfunction "GPIO27/ADC1_39") (pintype "bidirectional"))
    )
    (net (code "14") (name "A1_IN") (class "Default")
      (node (ref "IC3") (pin "1") (pinfunction "+IN_1") (pintype "input"))
      (node (ref "J1") (pin "1") (pinfunction "1_1") (pintype "bidirectional"))
    )
    (net (code "15") (name "A2") (class "Default")
      (node (ref "U5") (pin "40") (pinfunction "GPIO28/ADC2_40") (pintype "bidirectional"))
    )
    (net (code "16") (name "A3") (class "Default")
      (node (ref "U5") (pin "41") (pinfunction "GPIO29/ADC3_41") (pintype "bidirectional"))
    )
    (net (code "17") (name "BOOT") (class "Default")
      (node (ref "R3") (pin "1") (pinfunction "1_1") (pintype "passive"))
      (node (ref "SW1") (pin "2") (pinfunction "2_2") (pintype "passive"))
    )
    (net (code "18") (name "CHRG") (class "Default")
      (node (ref "D4") (pin "-") (pinfunction "-_-") (pintype "passive"))
      (node (ref "IC1") (pin "7") (pinfunction "CHRG_7") (pintype "bidirectional"))
    )
    (net (code "19") (name "D0{slash}TX0") (class "Default")
      (node (ref "R12") (pin "1") (pinfunction "1_1") (pintype "passive"))
      (node (ref "U5") (pin "2") (pinfunction "GPIO0_2") (pintype "bidirectional"))
    )
    (net (code "20") (name "D1{slash}RX0") (class "Default")
      (node (ref "R11") (pin "1") (pinfunction "1_1") (pintype "passive"))
      (node (ref "U5") (pin "3") (pinfunction "GPIO1_3") (pintype "bidirectional"))
    )
    (net (code "21") (name "D2") (class "Default")
      (node (ref "Q3") (pin "2") (pinfunction "S_2") (pintype "passive"))
      (node (ref "R38") (pin "1") (pinfunction "1_1") (pintype "passive"))
      (node (ref "U5") (pin "4") (pinfunction "GPIO2_4") (pintype "bidirectional"))
    )
    (net (code "22") (name "D2_H") (class "Default")
      (node (ref "J9") (pin "1") (pinfunction "1_1") (pintype "bidirectional"))
      (node (ref "Q3") (pin "3") (pinfunction "D_3") (pintype "passive"))
      (node (ref "R39") (pin "1") (pinfunction "1_1") (pintype "passive"))
    )
    (net (code "23") (name "D3") (class "Default")
      (node (ref "Q9") (pin "2") (pinfunction "S_2") (pintype "passive"))
      (node (ref "R22") (pin "1") (pinfunction "1_1") (pintype "passive"))
      (node (ref "U5") (pin "5") (pinfunction "GPIO3_5") (pintype "bidirectional"))
    )
    (net (code "24") (name "D3_H") (class "Default")
      (node (ref "J8") (pin "1") (pinfunction "1_1") (pintype "bidirectional"))
      (node (ref "Q9") (pin "3") (pinfunction "D_3") (pintype "passive"))
      (node (ref "R19") (pin "1") (pinfunction "1_1") (pintype "passive"))
    )
    (net (code "25") (name "D4{slash}SDA0") (class "Default")
      (node (ref "Q12") (pin "2") (pinfunction "S_2") (pintype "passive"))
      (node (ref "R44") (pin "1") (pinfunction "1_1") (pintype "passive"))
      (node (ref "U5") (pin "6") (pinfunction "GPIO4_6") (pintype "bidirectional"))
    )
    (net (code "26") (name "D4{slash}SDA0_H") (class "Default")
      (node (ref "J11") (pin "2") (pinfunction "2_2") (pintype "bidirectional"))
      (node (ref "Q12") (pin "3") (pinfunction "D_3") (pintype "passive"))
      (node (ref "R45") (pin "1") (pinfunction "1_1") (pintype "passive"))
    )
    (net (code "27") (name "D5{slash}SCL0") (class "Default")
      (node (ref "Q13") (pin "2") (pinfunction "S_2") (pintype "passive"))
      (node (ref "R46") (pin "1") (pinfunction "1_1") (pintype "passive"))
      (node (ref "U5") (pin "7") (pinfunction "GPIO5_7") (pintype "bidirectional"))
    )
    (net (code "28") (name "D5{slash}SCL0_H") (class "Default")
      (node (ref "J11") (pin "1") (pinfunction "1_1") (pintype "bidirectional"))
      (node (ref "Q13") (pin "3") (pinfunction "D_3") (pintype "passive"))
      (node (ref "R47") (pin "1") (pinfunction "1_1") (pintype "passive"))
    )
    (net (code "29") (name "D6") (class "Default")
      (node (ref "J3") (pin "3") (pinfunction "3_3") (pintype "passive"))
      (node (ref "U5") (pin "8") (pinfunction "GPIO6_8") (pintype "bidirectional"))
    )
    (net (code "30") (name "D7") (class "Default")
      (node (ref "J3") (pin "4") (pinfunction "4_4") (pintype "passive"))
      (node (ref "U5") (pin "9") (pinfunction "GPIO7_9") (pintype "bidirectional"))
    )
    (net (code "31") (name "D8{slash}TX1") (class "Default")
      (node (ref "Q10") (pin "2") (pinfunction "S_2") (pintype "passive"))
      (node (ref "R40") (pin "1") (pinfunction "1_1") (pintype "passive"))
      (node (ref "U5") (pin "11") (pinfunction "GPIO8_11") (pintype "bidirectional"))
    )
    (net (code "32") (name "D8{slash}TX1_H") (class "Default")
      (node (ref "J10") (pin "2") (pinfunction "2_2") (pintype "bidirectional"))
      (node (ref "Q10") (pin "3") (pinfunction "D_3") (pintype "passive"))
      (node (ref "R41") (pin "1") (pinfunction "1_1") (pintype "passive"))
    )
    (net (code "33") (name "D9{slash}RX1") (class "Default")
      (node (ref "Q11") (pin "2") (pinfunction "S_2") (pintype "passive"))
      (node (ref "R42") (pin "1") (pinfunction "1_1") (pintype "passive"))
      (node (ref "U5") (pin "12") (pinfunction "GPIO9_12") (pintype "bidirectional"))
    )
    (net (code "34") (name "D9{slash}RX1_H") (class "Default")
      (node (ref "J10") (pin "1") (pinfunction "1_1") (pintype "bidirectional"))
      (node (ref "Q11") (pin "3") (pinfunction "D_3") (pintype "passive"))
      (node (ref "R43") (pin "1") (pinfunction "1_1") (pintype "passive"))
    )
    (net (code "35") (name "D10") (class "Default")
      (node (ref "J3") (pin "5") (pinfunction "5_5") (pintype "passive"))
      (node (ref "U5") (pin "13") (pinfunction "GPIO10_13") (pintype "bidirectional"))
    )
    (net (code "36") (name "D11") (class "Default")
      (node (ref "J3") (pin "6") (pinfunction "6_6") (pintype "passive"))
      (node (ref "U5") (pin "14") (pinfunction "GPIO11_14") (pintype "bidirectional"))
    )
    (net (code "37") (name "D12") (class "Default")
      (node (ref "J3") (pin "7") (pinfunction "7_7") (pintype "passive"))
      (node (ref "U5") (pin "15") (pinfunction "GPIO12_15") (pintype "bidirectional"))
    )
    (net (code "38") (name "D13") (class "Default")
      (node (ref "J3") (pin "8") (pinfunction "8_8") (pintype "passive"))
      (node (ref "U5") (pin "16") (pinfunction "GPIO13_16") (pintype "bidirectional"))
    )
    (net (code "39") (name "D14") (class "Default")
      (node (ref "J3") (pin "9") (pinfunction "9_9") (pintype "passive"))
      (node (ref "U5") (pin "17") (pinfunction "GPIO14_17") (pintype "bidirectional"))
    )
    (net (code "40") (name "D15") (class "Default")
      (node (ref "J3") (pin "10") (pinfunction "10_10") (pintype "passive"))
      (node (ref "U5") (pin "18") (pinfunction "GPIO15_18") (pintype "bidirectional"))
    )
    (net (code "41") (name "D16") (class "Default")
      (node (ref "J3") (pin "11") (pinfunction "11_11") (pintype "passive"))
      (node (ref "U5") (pin "27") (pinfunction "GPIO16_27") (pintype "bidirectional"))
    )
    (net (code "42") (name "D17") (class "Default")
      (node (ref "J3") (pin "12") (pinfunction "12_12") (pintype "passive"))
      (node (ref "U5") (pin "28") (pinfunction "GPIO17_28") (pintype "bidirectional"))
    )
    (net (code "43") (name "D18") (class "Default")
      (node (ref "J3") (pin "13") (pinfunction "13_13") (pintype "passive"))
      (node (ref "U5") (pin "29") (pinfunction "GPIO18_29") (pintype "bidirectional"))
    )
    (net (code "44") (name "D19") (class "Default")
      (node (ref "J3") (pin "14") (pinfunction "14_14") (pintype "passive"))
      (node (ref "U5") (pin "30") (pinfunction "GPIO19_30") (pintype "bidirectional"))
    )
    (net (code "45") (name "D20") (class "Default")
      (node (ref "J3") (pin "15") (pinfunction "15_15") (pintype "passive"))
      (node (ref "U5") (pin "31") (pinfunction "GPIO20_31") (pintype "bidirectional"))
    )
    (net (code "46") (name "D21") (class "Default")
      (node (ref "J3") (pin "16") (pinfunction "16_16") (pintype "passive"))
      (node (ref "U5") (pin "32") (pinfunction "GPIO21_32") (pintype "bidirectional"))
    )
    (net (code "47") (name "D22") (class "Default")
      (node (ref "J3") (pin "17") (pinfunction "17_17") (pintype "passive"))
      (node (ref "U5") (pin "34") (pinfunction "GPIO22_34") (pintype "bidirectional"))
    )
    (net (code "48") (name "D23") (class "Default")
      (node (ref "J3") (pin "18") (pinfunction "18_18") (pintype "passive"))
      (node (ref "U5") (pin "35") (pinfunction "GPIO23_35") (pintype "bidirectional"))
    )
    (net (code "49") (name "D24") (class "Default")
      (node (ref "J3") (pin "19") (pinfunction "19_19") (pintype "passive"))
      (node (ref "U5") (pin "36") (pinfunction "GPIO24_36") (pintype "bidirectional"))
    )
    (net (code "50") (name "D25") (class "Default")
      (node (ref "D1") (pin "-") (pinfunction "-_-") (pintype "passive"))
      (node (ref "J3") (pin "20") (pinfunction "20_20") (pintype "passive"))
      (node (ref "U5") (pin "37") (pinfunction "GPIO25_37") (pintype "bidirectional"))
    )
    (net (code "51") (name "DN") (class "Default")
      (node (ref "J5") (pin "A7") (pinfunction "A7_A7") (pintype "bidirectional"))
      (node (ref "J5") (pin "B7") (pinfunction "B7_B7") (pintype "bidirectional"))
      (node (ref "R5") (pin "1") (pinfunction "1_1") (pintype "passive"))
    )
    (net (code "52") (name "DP") (class "Default")
      (node (ref "J5") (pin "A6") (pinfunction "A6_A6") (pintype "bidirectional"))
      (node (ref "J5") (pin "B6") (pinfunction "B6_B6") (pintype "bidirectional"))
      (node (ref "R6") (pin "1") (pinfunction "1_1") (pintype "passive"))
    )
    (net (code "53") (name "LR_BOOT") (class "Default")
      (node (ref "R2") (pin "1") (pinfunction "1_1") (pintype "passive"))
      (node (ref "SW3") (pin "1") (pinfunction "1_1") (pintype "passive"))
      (node (ref "U4") (pin "2") (pinfunction "BOOT_2") (pintype "bidirectional"))
    )
    (net (code "54") (name "NRST") (class "Default")
      (node (ref "C19") (pin "2") (pinfunction "2_2") (pintype "passive"))
      (node (ref "D5") (pin "+") (pinfunction "+_+") (pintype "passive"))
      (node (ref "R10") (pin "2") (pinfunction "2_2") (pintype "passive"))
      (node (ref "U4") (pin "3") (pinfunction "NRST_3") (pintype "bidirectional"))
    )
    (net (code "55") (name "Net-(ANT1-SIGNAL)") (class "Default")
      (node (ref "ANT1") (pin "P$3") (pinfunction "SIGNAL_P$3") (pintype "bidirectional"))
      (node (ref "U4") (pin "33") (pinfunction "RF_ANT_33") (pintype "bidirectional"))
    )
    (net (code "56") (name "Net-(D1-Pad+)") (class "Default")
      (node (ref "D1") (pin "+") (pinfunction "+_+") (pintype "passive"))
      (node (ref "R17") (pin "1") (pinfunction "1_1") (pintype "passive"))
    )
    (net (code "57") (name "Net-(D4-Pad+)") (class "Default")
      (node (ref "D4") (pin "+") (pinfunction "+_+") (pintype "passive"))
      (node (ref "R18") (pin "1") (pinfunction "1_1") (pintype "passive"))
    )
    (net (code "58") (name "Net-(IC1-ISET)") (class "Default")
      (node (ref "IC1") (pin "2") (pinfunction "ISET_2") (pintype "bidirectional"))
      (node (ref "R15") (pin "2") (pinfunction "2_2") (pintype "passive"))
    )
    (net (code "59") (name "Net-(J5-PadA5)") (class "Default")
      (node (ref "J5") (pin "A5") (pinfunction "A5_A5") (pintype "bidirectional"))
      (node (ref "R8") (pin "2") (pinfunction "2_2") (pintype "passive"))
    )
    (net (code "60") (name "Net-(J5-PadB5)") (class "Default")
      (node (ref "J5") (pin "B5") (pinfunction "B5_B5") (pintype "bidirectional"))
      (node (ref "R7") (pin "1") (pinfunction "1_1") (pintype "passive"))
    )
    (net (code "61") (name "Net-(R14-Pad2)") (class "Default")
      (node (ref "R14") (pin "2") (pinfunction "2_2") (pintype "passive"))
      (node (ref "SW3") (pin "2") (pinfunction "2_2") (pintype "passive"))
    )
    (net (code "62") (name "Net-(U1-FB)") (class "Default")
      (node (ref "R16") (pin "2") (pinfunction "2_2") (pintype "passive"))
      (node (ref "R21") (pin "1") (pinfunction "1_1") (pintype "passive"))
      (node (ref "U1") (pin "3") (pinfunction "FB_3") (pintype "bidirectional"))
    )
    (net (code "63") (name "Net-(U1-LX)") (class "Default")
      (node (ref "D6") (pin "+") (pinfunction "+_+") (pintype "passive"))
      (node (ref "L2") (pin "2") (pinfunction "2_2") (pintype "passive"))
      (node (ref "U1") (pin "1") (pinfunction "LX_1") (pintype "bidirectional"))
    )
    (net (code "64") (name "Net-(U2-FB)") (class "Default")
      (node (ref "R23") (pin "1") (pinfunction "1_1") (pintype "passive"))
      (node (ref "R37") (pin "2") (pinfunction "2_2") (pintype "passive"))
      (node (ref "U2") (pin "5") (pinfunction "FB_5") (pintype "bidirectional"))
    )
    (net (code "65") (name "Net-(U2-SW)") (class "Default")
      (node (ref "L1") (pin "1") (pinfunction "1_1") (pintype "passive"))
      (node (ref "U2") (pin "3") (pinfunction "SW_3") (pintype "bidirectional"))
    )
    (net (code "66") (name "Net-(U5-ADC_VDD)") (class "Default")
      (node (ref "C1") (pin "2") (pinfunction "2_2") (pintype "passive"))
      (node (ref "R1") (pin "2") (pinfunction "2_2") (pintype "passive"))
      (node (ref "U5") (pin "43") (pinfunction "ADC_VDD_43") (pintype "bidirectional"))
    )
    (net (code "67") (name "POWER_GND") (class "Default")
      (node (ref "ANT1") (pin "P$1") (pinfunction "GND_P$1") (pintype "bidirectional"))
      (node (ref "ANT1") (pin "P$2") (pinfunction "GND_P$2") (pintype "bidirectional"))
      (node (ref "C1") (pin "1") (pinfunction "1_1") (pintype "passive"))
      (node (ref "C10") (pin "1") (pinfunction "1_1") (pintype "passive"))
      (node (ref "C11") (pin "1") (pinfunction "1_1") (pintype "passive"))
      (node (ref "C12") (pin "1") (pinfunction "1_1") (pintype "passive"))
      (node (ref "C13") (pin "1") (pinfunction "1_1") (pintype "passive"))
      (node (ref "C14") (pin "1") (pinfunction "1_1") (pintype "passive"))
      (node (ref "C15") (pin "1") (pinfunction "1_1") (pintype "passive"))
      (node (ref "C17") (pin "1") (pinfunction "1_1") (pintype "passive"))
      (node (ref "C19") (pin "1") (pinfunction "1_1") (pintype "passive"))
      (node (ref "C2") (pin "1") (pinfunction "1_1") (pintype "passive"))
      (node (ref "C20") (pin "1") (pinfunction "1_1") (pintype "passive"))
      (node (ref "C21") (pin "1") (pinfunction "1_1") (pintype "passive"))
      (node (ref "C22") (pin "1") (pinfunction "1_1") (pintype "passive"))
      (node (ref "C23") (pin "1") (pinfunction "1_1") (pintype "passive"))
      (node (ref "C24") (pin "1") (pinfunction "1_1") (pintype "passive"))
      (node (ref "C25") (pin "1") (pinfunction "1_1") (pintype "passive"))
      (node (ref "C26") (pin "1") (pinfunction "1_1") (pintype "passive"))
      (node (ref "C27") (pin "1") (pinfunction "1_1") (pintype "passive"))
      (node (ref "C28") (pin "1") (pinfunction "1_1") (pintype "passive"))
      (node (ref "C29") (pin "1") (pinfunction "1_1") (pintype "passive"))
      (node (ref "C3") (pin "1") (pinfunction "1_1") (pintype "passive"))
      (node (ref "C30") (pin "1") (pinfunction "1_1") (pintype "passive"))
      (node (ref "C31") (pin "1") (pinfunction "1_1") (pintype "passive"))
      (node (ref "C32") (pin "1") (pinfunction "1_1") (pintype "passive"))
      (node (ref "C33") (pin "1") (pinfunction "1_1") (pintype "passive"))
      (node (ref "C34") (pin "1") (pinfunction "1_1") (pintype "passive"))
      (node (ref "C4") (pin "1") (pinfunction "1_1") (pintype "passive"))
      (node (ref "C5") (pin "1") (pinfunction "1_1") (pintype "passive"))
      (node (ref "C6") (pin "1") (pinfunction "1_1") (pintype "passive"))
      (node (ref "C7") (pin "1") (pinfunction "1_1") (pintype "passive"))
      (node (ref "C8") (pin "1") (pinfunction "1_1") (pintype "passive"))
      (node (ref "C9") (pin "1") (pinfunction "1_1") (pintype "passive"))
      (node (ref "IC1") (pin "1") (pinfunction "TEMP_1") (pintype "bidirectional"))
      (node (ref "IC1") (pin "3") (pinfunction "GND_3") (pintype "bidirectional"))
      (node (ref "IC1") (pin "6") (pinfunction "DONE_6") (pintype "bidirectional"))
      (node (ref "IC1") (pin "PAD") (pinfunction "EP_PAD") (pintype "bidirectional"))
      (node (ref "IC2") (pin "2") (pinfunction "GND_2") (pintype "bidirectional"))
      (node (ref "IC3") (pin "2") (pinfunction "V-_2") (pintype "power_in"))
      (node (ref "IC4") (pin "2") (pinfunction "V-_2") (pintype "power_in"))
      (node (ref "J1") (pin "4") (pinfunction "4_4") (pintype "bidirectional"))
      (node (ref "J1") (pin "SS1") (pinfunction "SS1_SS1") (pintype "bidirectional"))
      (node (ref "J1") (pin "SS2") (pinfunction "SS2_SS2") (pintype "bidirectional"))
      (node (ref "J10") (pin "4") (pinfunction "4_4") (pintype "bidirectional"))
      (node (ref "J10") (pin "SS1") (pinfunction "SS1_SS1") (pintype "bidirectional"))
      (node (ref "J10") (pin "SS2") (pinfunction "SS2_SS2") (pintype "bidirectional"))
      (node (ref "J11") (pin "4") (pinfunction "4_4") (pintype "bidirectional"))
      (node (ref "J11") (pin "SS1") (pinfunction "SS1_SS1") (pintype "bidirectional"))
      (node (ref "J11") (pin "SS2") (pinfunction "SS2_SS2") (pintype "bidirectional"))
      (node (ref "J3") (pin "1") (pinfunction "1_1") (pintype "passive"))
      (node (ref "J4") (pin "P$2") (pinfunction "P$2_P$2") (pintype "bidirectional"))
      (node (ref "J4") (pin "P$3") (pinfunction "P$3_P$3") (pintype "bidirectional"))
      (node (ref "J4") (pin "P$4") (pinfunction "P$4_P$4") (pintype "bidirectional"))
      (node (ref "J5") (pin "A1") (pinfunction "A1_A1") (pintype "bidirectional"))
      (node (ref "J5") (pin "A12") (pinfunction "A12_A12") (pintype "bidirectional"))
      (node (ref "J5") (pin "B1") (pinfunction "B1_B1") (pintype "bidirectional"))
      (node (ref "J5") (pin "B12") (pinfunction "B12_B12") (pintype "bidirectional"))
      (node (ref "J5") (pin "P$1") (pinfunction "P$17_P$1") (pintype "bidirectional"))
      (node (ref "J5") (pin "P$2") (pinfunction "P$18_P$2") (pintype "bidirectional"))
      (node (ref "J5") (pin "P$3") (pinfunction "P$19_P$3") (pintype "bidirectional"))
      (node (ref "J5") (pin "P$4") (pinfunction "P$20_P$4") (pintype "bidirectional"))
      (node (ref "J6") (pin "P$2") (pinfunction "P$2_P$2") (pintype "bidirectional"))
      (node (ref "J6") (pin "P$3") (pinfunction "P$3_P$3") (pintype "bidirectional"))
      (node (ref "J6") (pin "P$4") (pinfunction "P$4_P$4") (pintype "bidirectional"))
      (node (ref "J7") (pin "4") (pinfunction "4_4") (pintype "bidirectional"))
      (node (ref "J7") (pin "SS1") (pinfunction "SS1_SS1") (pintype "bidirectional"))
      (node (ref "J7") (pin "SS2") (pinfunction "SS2_SS2") (pintype "bidirectional"))
      (node (ref "J8") (pin "4") (pinfunction "4_4") (pintype "bidirectional"))
      (node (ref "J8") (pin "SS1") (pinfunction "SS1_SS1") (pintype "bidirectional"))
      (node (ref "J8") (pin "SS2") (pinfunction "SS2_SS2") (pintype "bidirectional"))
      (node (ref "J9") (pin "4") (pinfunction "4_4") (pintype "bidirectional"))
      (node (ref "J9") (pin "SS1") (pinfunction "SS1_SS1") (pintype "bidirectional"))
      (node (ref "J9") (pin "SS2") (pinfunction "SS2_SS2") (pintype "bidirectional"))
      (node (ref "P4") (pin "P$1") (pinfunction "P$1_P$1") (pintype "bidirectional"))
      (node (ref "R15") (pin "1") (pinfunction "1_1") (pintype "passive"))
      (node (ref "R2") (pin "2") (pinfunction "2_2") (pintype "passive"))
      (node (ref "R21") (pin "2") (pinfunction "2_2") (pintype "passive"))
      (node (ref "R24") (pin "2") (pinfunction "2_2") (pintype "passive"))
      (node (ref "R26") (pin "2") (pinfunction "2_2") (pintype "passive"))
      (node (ref "R36") (pin "2") (pinfunction "2_2") (pintype "passive"))
      (node (ref "R37") (pin "1") (pinfunction "1_1") (pintype "passive"))
      (node (ref "R7") (pin "2") (pinfunction "2_2") (pintype "passive"))
      (node (ref "R8") (pin "1") (pinfunction "1_1") (pintype "passive"))
      (node (ref "R9") (pin "2") (pinfunction "2_2") (pintype "passive"))
      (node (ref "SW1") (pin "1") (pinfunction "1_1") (pintype "passive"))
      (node (ref "SW2") (pin "1") (pinfunction "1_1") (pintype "passive"))
      (node (ref "U1") (pin "2") (pinfunction "GND_2") (pintype "bidirectional"))
      (node (ref "U2") (pin "2") (pinfunction "GND_2") (pintype "bidirectional"))
      (node (ref "U4") (pin "1") (pinfunction "GND_1") (pintype "bidirectional"))
      (node (ref "U4") (pin "10") (pinfunction "GND_10") (pintype "bidirectional"))
      (node (ref "U4") (pin "34") (pinfunction "GND_34") (pintype "bidirectional"))
      (node (ref "U4") (pin "4") (pinfunction "GND_4") (pintype "bidirectional"))
      (node (ref "U4") (pin "5") (pinfunction "GND_5") (pintype "bidirectional"))
      (node (ref "U4") (pin "9") (pinfunction "GND_9") (pintype "bidirectional"))
      (node (ref "U5") (pin "19") (pinfunction "TESTEN_19") (pintype "bidirectional"))
      (node (ref "U5") (pin "EPAD") (pinfunction "GND_EPAD") (pintype "bidirectional"))
      (node (ref "U6") (pin "4") (pinfunction "GND_4") (pintype "bidirectional"))
      (node (ref "X1") (pin "2") (pinfunction "GND_2") (pintype "bidirectional"))
      (node (ref "X1") (pin "4") (pinfunction "GND_4") (pintype "bidirectional"))
    )
    (net (code "68") (name "QSPI_CS") (class "Default")
      (node (ref "R3") (pin "2") (pinfunction "2_2") (pintype "passive"))
      (node (ref "R4") (pin "2") (pinfunction "2_2") (pintype "passive"))
      (node (ref "U5") (pin "56") (pinfunction "QSPI_~{CS}_56") (pintype "bidirectional"))
      (node (ref "U6") (pin "1") (pinfunction "/CS_1") (pintype "bidirectional"))
    )
    (net (code "69") (name "QSPI_D0") (class "Default")
      (node (ref "U5") (pin "53") (pinfunction "QSPI_SD0_53") (pintype "bidirectional"))
      (node (ref "U6") (pin "5") (pinfunction "DI(IO0)_5") (pintype "bidirectional"))
    )
    (net (code "70") (name "QSPI_D1") (class "Default")
      (node (ref "U5") (pin "55") (pinfunction "QSPI_SD1_55") (pintype "bidirectional"))
      (node (ref "U6") (pin "2") (pinfunction "DO(IO1)_2") (pintype "bidirectional"))
    )
    (net (code "71") (name "QSPI_D2") (class "Default")
      (node (ref "U5") (pin "54") (pinfunction "QSPI_SD2_54") (pintype "bidirectional"))
      (node (ref "U6") (pin "3") (pinfunction "/WP(IO2)_3") (pintype "bidirectional"))
    )
    (net (code "72") (name "QSPI_D3") (class "Default")
      (node (ref "U5") (pin "51") (pinfunction "QSPI_SD3_51") (pintype "bidirectional"))
      (node (ref "U6") (pin "7") (pinfunction "/HOLD/RESET(IO3)_7") (pintype "bidirectional"))
    )
    (net (code "73") (name "QSPI_SCK") (class "Default")
      (node (ref "U5") (pin "52") (pinfunction "QSPI_SCLK_52") (pintype "bidirectional"))
      (node (ref "U6") (pin "6") (pinfunction "CLK_6") (pintype "bidirectional"))
    )
    (net (code "74") (name "RESET") (class "Default")
      (node (ref "C14") (pin "2") (pinfunction "2_2") (pintype "passive"))
      (node (ref "D5") (pin "-") (pinfunction "-_-") (pintype "passive"))
      (node (ref "R13") (pin "2") (pinfunction "2_2") (pintype "passive"))
      (node (ref "SW2") (pin "2") (pinfunction "2_2") (pintype "passive"))
      (node (ref "U5") (pin "26") (pinfunction "RUN_26") (pintype "bidirectional"))
    )
    (net (code "75") (name "RF_3V3") (class "Default")
      (node (ref "C26") (pin "2") (pinfunction "2_2") (pintype "passive"))
      (node (ref "C27") (pin "2") (pinfunction "2_2") (pintype "passive"))
      (node (ref "IC2") (pin "5") (pinfunction "VOUT_5") (pintype "bidirectional"))
      (node (ref "P3") (pin "P$1") (pinfunction "P$1_P$1") (pintype "bidirectional"))
      (node (ref "R10") (pin "1") (pinfunction "1_1") (pintype "passive"))
      (node (ref "R14") (pin "1") (pinfunction "1_1") (pintype "passive"))
      (node (ref "U4") (pin "32") (pinfunction "3V3_32") (pintype "bidirectional"))
    )
    (net (code "76") (name "RF_RX") (class "Default")
      (node (ref "P2") (pin "P$1") (pinfunction "P$1_P$1") (pintype "bidirectional"))
      (node (ref "R12") (pin "2") (pinfunction "2_2") (pintype "passive"))
      (node (ref "U4") (pin "26") (pinfunction "LPUART-RX_26") (pintype "bidirectional"))
    )
    (net (code "77") (name "RF_TX") (class "Default")
      (node (ref "P1") (pin "P$1") (pinfunction "P$1_P$1") (pintype "bidirectional"))
      (node (ref "R11") (pin "2") (pinfunction "2_2") (pintype "passive"))
      (node (ref "U4") (pin "25") (pinfunction "LPUART-TX_25") (pintype "bidirectional"))
    )
    (net (code "78") (name "SWCLK") (class "Default")
      (node (ref "U5") (pin "24") (pinfunction "SWCLK_24") (pintype "bidirectional"))
    )
    (net (code "79") (name "SWDIO") (class "Default")
      (node (ref "U5") (pin "25") (pinfunction "SWDIO_25") (pintype "bidirectional"))
    )
    (net (code "80") (name "USB_D+") (class "Default")
      (node (ref "R6") (pin "2") (pinfunction "2_2") (pintype "passive"))
      (node (ref "U5") (pin "47") (pinfunction "USB_D+_47") (pintype "bidirectional"))
    )
    (net (code "81") (name "USB_D-") (class "Default")
      (node (ref "R5") (pin "2") (pinfunction "2_2") (pintype "passive"))
      (node (ref "U5") (pin "46") (pinfunction "USB_D-_46") (pintype "bidirectional"))
    )
    (net (code "82") (name "XIN") (class "Default")
      (node (ref "C3") (pin "2") (pinfunction "2_2") (pintype "passive"))
      (node (ref "U5") (pin "20") (pinfunction "XIN_20") (pintype "bidirectional"))
      (node (ref "X1") (pin "1") (pinfunction "XIN_1") (pintype "bidirectional"))
    )
    (net (code "83") (name "XOUT") (class "Default")
      (node (ref "C4") (pin "2") (pinfunction "2_2") (pintype "passive"))
      (node (ref "U5") (pin "21") (pinfunction "XOUT_21") (pintype "bidirectional"))
      (node (ref "X1") (pin "3") (pinfunction "XOUT_3") (pintype "bidirectional"))
    )
    (net (code "84") (name "unconnected-(IC2-NC-Pad4)") (class "Default")
      (node (ref "IC2") (pin "4") (pinfunction "NC_4") (pintype "bidirectional"))
    )
    (net (code "85") (name "unconnected-(J1-Pad2)") (class "Default")
      (node (ref "J1") (pin "2") (pinfunction "2_2") (pintype "bidirectional"))
    )
    (net (code "86") (name "unconnected-(J5-PadA8)") (class "Default")
      (node (ref "J5") (pin "A8") (pinfunction "A8_A8") (pintype "bidirectional"))
    )
    (net (code "87") (name "unconnected-(J5-PadB8)") (class "Default")
      (node (ref "J5") (pin "B8") (pinfunction "B8_B8") (pintype "bidirectional"))
    )
    (net (code "88") (name "unconnected-(J7-Pad2)") (class "Default")
      (node (ref "J7") (pin "2") (pinfunction "2_2") (pintype "bidirectional"))
    )
    (net (code "89") (name "unconnected-(J8-Pad2)") (class "Default")
      (node (ref "J8") (pin "2") (pinfunction "2_2") (pintype "bidirectional"))
    )
    (net (code "90") (name "unconnected-(J9-Pad2)") (class "Default")
      (node (ref "J9") (pin "2") (pinfunction "2_2") (pintype "bidirectional"))
    )
    (net (code "91") (name "unconnected-(U1-OC-Pad6)") (class "Default")
      (node (ref "U1") (pin "6") (pinfunction "OC_6") (pintype "bidirectional"))
    )
  )
)
